# final_sch.net
KiCad netlist of a schematic drawn in Altium Designer
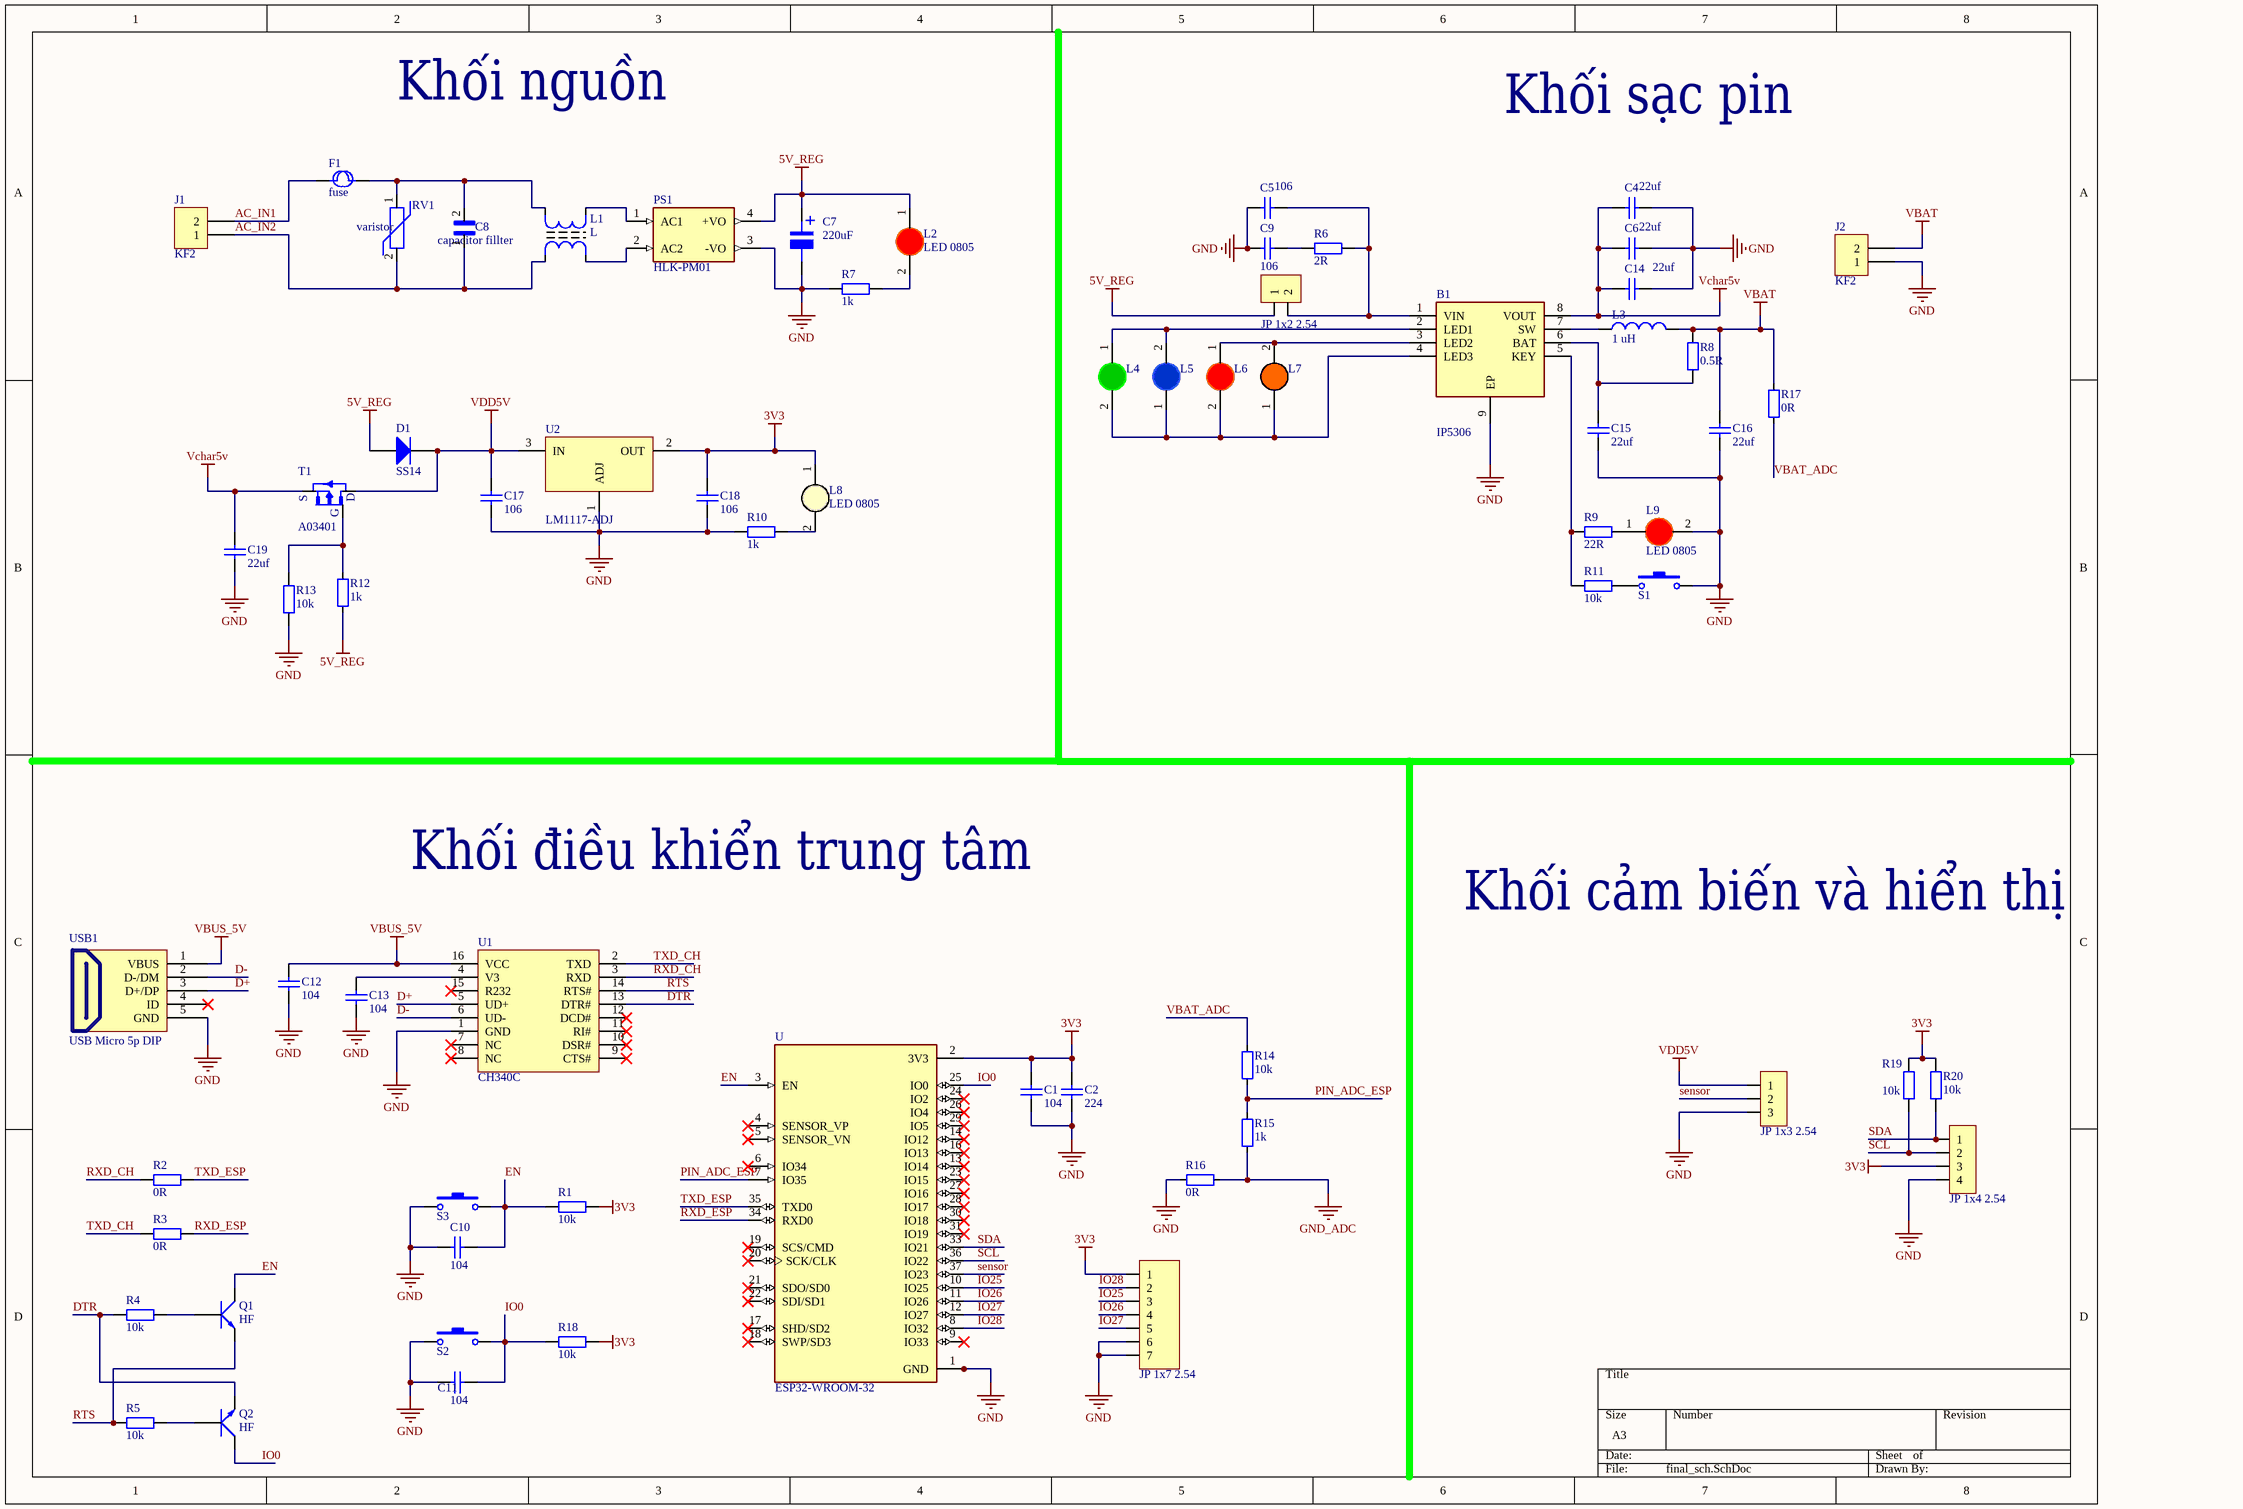
[diagram p0: final_sch.SchDoc]

(export (version "E")
  (design (tool "Eeschema 10.0.6"))
  (components
    (comp (ref "B1")
      (value "IP5306")
      (footprint "SOIC127P600X165-9N")
      (description "Fully-Integrated Power-Bank System-On-Chip")
      (libsource (lib "IP5306") (part "IP5306"))
    )
    (comp (ref "C1")
      (value "104")
      (footprint "tu 0805")
      (description "Dán")
      (libsource (lib "Altium_Lib_by_KhueNguyenCreator") (part "Tu 0805 104 50V 10%"))
    )
    (comp (ref "C2")
      (value "224")
      (footprint "tu 0805")
      (description "Dán")
      (libsource (lib "Altium_Lib_by_KhueNguyenCreator") (part "Tu 0805 224 50V 10%"))
    )
    (comp (ref "C4")
      (value "22uf")
      (footprint "tu 0805")
      (description "Dán")
      (libsource (lib "Altium_Lib_by_KhueNguyenCreator") (part "Tu 0805 225 25V 10%"))
    )
    (comp (ref "C5")
      (value "106")
      (footprint "tu 0805")
      (description "Dán")
      (libsource (lib "Altium_Lib_by_KhueNguyenCreator") (part "Tu 0805 106 16V 10%"))
    )
    (comp (ref "C6")
      (value "22uf")
      (footprint "tu 0805")
      (description "Dán")
      (libsource (lib "Altium_Lib_by_KhueNguyenCreator") (part "Tu 0805 225 25V 10%"))
    )
    (comp (ref "C7")
      (value "220uF")
      (footprint "tu nhom 10 (g)")
      (description "Dán")
      (libsource (lib "Altium_Lib_by_KhueNguyenCreator") (part "Tu Nhom 220uF 50V"))
    )
    (comp (ref "C8")
      (value "capacitor fillter")
      (footprint "CAPRR1000W60L1300T600H1200")
      (description "Safety Capacitors FILM CAP MKP X2 0.10uF 20% 305Vac LS 10mm - short leads")
      (fields (field (name "MP") "B32921C3104M003") (field (name "MF") "TDK"))
      (libsource (lib "B32921C3104M003") (part "B32921C3104M003"))
    )
    (comp (ref "C9")
      (value "106")
      (footprint "tu 0805")
      (description "Dán")
      (libsource (lib "Altium_Lib_by_KhueNguyenCreator") (part "Tu 0805 106 16V 10%"))
    )
    (comp (ref "C10")
      (value "104")
      (footprint "tu 0805")
      (description "Dán")
      (libsource (lib "Altium_Lib_by_KhueNguyenCreator") (part "Tu 0805 104 50V 10%"))
    )
    (comp (ref "C11")
      (value "104")
      (footprint "tu 0805")
      (description "Dán")
      (libsource (lib "Altium_Lib_by_KhueNguyenCreator") (part "Tu 0805 104 50V 10%"))
    )
    (comp (ref "C12")
      (value "104")
      (footprint "tu 0805")
      (description "Dán")
      (libsource (lib "Altium_Lib_by_KhueNguyenCreator") (part "Tu 0805 104 50V 10%"))
    )
    (comp (ref "C13")
      (value "104")
      (footprint "tu 0805")
      (description "Dán")
      (libsource (lib "Altium_Lib_by_KhueNguyenCreator") (part "Tu 0805 104 50V 10%"))
    )
    (comp (ref "C14")
      (value "22uf")
      (footprint "tu 0805")
      (description "Dán")
      (libsource (lib "Altium_Lib_by_KhueNguyenCreator") (part "Tu 0805 225 25V 10%"))
    )
    (comp (ref "C15")
      (value "22uf")
      (footprint "tu 0805")
      (description "Dán")
      (libsource (lib "Altium_Lib_by_KhueNguyenCreator") (part "Tu 0805 225 25V 10%"))
    )
    (comp (ref "C16")
      (value "22uf")
      (footprint "tu 0805")
      (description "Dán")
      (libsource (lib "Altium_Lib_by_KhueNguyenCreator") (part "Tu 0805 225 25V 10%"))
    )
    (comp (ref "C17")
      (value "106")
      (footprint "tu 0805")
      (description "Dán")
      (libsource (lib "Altium_Lib_by_KhueNguyenCreator") (part "Tu 0805 106 16V 10%"))
    )
    (comp (ref "C18")
      (value "106")
      (footprint "tu 0805")
      (description "Dán")
      (libsource (lib "Altium_Lib_by_KhueNguyenCreator") (part "Tu 0805 106 16V 10%"))
    )
    (comp (ref "C19")
      (value "22uf")
      (footprint "tu 0805")
      (description "Dán")
      (libsource (lib "Altium_Lib_by_KhueNguyenCreator") (part "Tu 0805 225 25V 10%"))
    )
    (comp (ref "D1")
      (value "SS14")
      (footprint "DIODE SMA")
      (description "Dán")
      (libsource (lib "Altium_Lib_by_KhueNguyenCreator") (part "Diode SS14 ( 1N5819)"))
    )
    (comp (ref "F1")
      (value "fuse")
      (footprint "F2-5.1-11.4X3.0X18.3MM")
      (description "Polymeric PTC Resettable Fuse 30V 2.5A Ih Through Hole Radial, Disc")
      (fields (field (name "MF") "Littelfuse") (field (name "MP") "30R250"))
      (libsource (lib "DIP-PPTC-2.5A-30V_D11.4MM_") (part "DIP-PPTC-2.5A-30V(D11.4MM)"))
    )
    (comp (ref "J1")
      (value "KF2")
      (footprint "KF2-3.5")
      (fields
        (field (name "MANUFACTURER") "Würth Elektronik eiSos GmbH")
        (field (name "PARTNO") "691103110002")
        (field (name "CREATED BY") "Karrer Zheng")
      )
      (libsource (lib "My Library") (part "KF2"))
    )
    (comp (ref "J2")
      (value "KF2")
      (footprint "KF2-3.5")
      (fields
        (field (name "MANUFACTURER") "Würth Elektronik eiSos GmbH")
        (field (name "PARTNO") "691103110002")
        (field (name "CREATED BY") "Karrer Zheng")
      )
      (libsource (lib "My Library") (part "KF2"))
    )
    (comp (ref "JP1")
      (value "JP 1x4 2.54")
      (footprint "JP 1x4 CT")
      (description "Cắm")
      (libsource (lib "Altium_Lib_by_KhueNguyenCreator") (part "JP 1x4 2.54 Cai Thang"))
    )
    (comp (ref "JP2")
      (value "JP 1x3 2.54")
      (footprint "JP 1x3 DT")
      (description "Cắm")
      (libsource (lib "Altium_Lib_by_KhueNguyenCreator") (part "JP 1x3 2.54 Duc Thang"))
    )
    (comp (ref "JP3")
      (value "JP 1x7 2.54")
      (footprint "JP 1x7 CT")
      (description "Cắm")
      (libsource (lib "Altium_Lib_by_KhueNguyenCreator") (part "JP 1x7 2.54 Cai Thang"))
    )
    (comp (ref "JP4")
      (value "JP 1x2 2.54")
      (footprint "JP 1x2 DT")
      (description "Cắm")
      (libsource (lib "Altium_Lib_by_KhueNguyenCreator") (part "JP 1x2 2.54 Duc Thang"))
    )
    (comp (ref "L1")
      (value "L")
      (footprint "L-DIP-220")
      (description "Inductor")
      (fields (field (name "DESIGNED BY") "VanDungEvn"))
      (libsource (lib "My Library") (part "L-DIP-220"))
    )
    (comp (ref "L2")
      (value "LED 0805")
      (footprint "LED-0805-Red")
      (description "Dán")
      (libsource (lib "Altium_Lib_by_KhueNguyenCreator") (part "LED 0805 Do"))
    )
    (comp (ref "L3")
      (value "1 uH")
      (footprint "IND_90.5_141.7_125X31_SMD")
      (description "Fixed Inductors WPN3012H1R0MT 100kHz")
      (fields
        (field (name "MANUFACTURER") "Sunlord")
        (field (name "MANUFACTURER PART NUMBER") "WPN3012H1R0MT")
      )
      (libsource (lib "Altium_Lib_by_KhueNguyenCreator") (part "IND_1uH-4.2A-20%-SMD"))
    )
    (comp (ref "L4")
      (value "~")
      (footprint "LED-0805-Green")
      (description "Dán")
      (libsource (lib "Altium_Lib_by_KhueNguyenCreator") (part "LED 0805 Xanh La"))
    )
    (comp (ref "L5")
      (value "~")
      (footprint "LED-0805-Blue")
      (description "Dán")
      (libsource (lib "Altium_Lib_by_KhueNguyenCreator") (part "LED 0805 Xanh Duong"))
    )
    (comp (ref "L6")
      (value "~")
      (footprint "LED-0805-Red")
      (description "Dán")
      (libsource (lib "Altium_Lib_by_KhueNguyenCreator") (part "LED 0805 Do"))
    )
    (comp (ref "L7")
      (value "~")
      (footprint "LED-0805-Orange")
      (description "Dán")
      (libsource (lib "Altium_Lib_by_KhueNguyenCreator") (part "LED 0805 Cam"))
    )
    (comp (ref "L8")
      (value "LED 0805")
      (footprint "LED-0805-Yellow")
      (description "Dán")
      (libsource (lib "Altium_Lib_by_KhueNguyenCreator") (part "LED 0805 Trang"))
    )
    (comp (ref "L9")
      (value "LED 0805")
      (footprint "LED-0805-Red")
      (description "Dán")
      (libsource (lib "Altium_Lib_by_KhueNguyenCreator") (part "LED 0805 Do"))
    )
    (comp (ref "PS1")
      (value "HLK-PM01")
      (footprint "CONV_HLK-PM01")
      (fields (field (name "MF") "Hi-link") (field (name "MP") "hlk-pm01"))
      (libsource (lib "HLK-PM01") (part "HLK-PM01"))
    )
    (comp (ref "Q1")
      (value "HF")
      (footprint "SOT23")
      (description "NPN transistor")
      (libsource (lib "Altium_Lib_by_KhueNguyenCreator") (part "C1815 HF SMD"))
    )
    (comp (ref "Q2")
      (value "HF")
      (footprint "SOT23")
      (description "NPN transistor")
      (libsource (lib "Altium_Lib_by_KhueNguyenCreator") (part "C1815 HF SMD"))
    )
    (comp (ref "R1")
      (value "10k")
      (footprint "tro smd 0805")
      (description "Dán")
      (libsource (lib "Altium_Lib_by_KhueNguyenCreator") (part "Tro 0805 5% 10k"))
    )
    (comp (ref "R2")
      (value "0R")
      (footprint "tro smd 0805")
      (description "Dán")
      (libsource (lib "Altium_Lib_by_KhueNguyenCreator") (part "Tro 0805 5% 0R"))
    )
    (comp (ref "R3")
      (value "0R")
      (footprint "tro smd 0805")
      (description "Dán")
      (libsource (lib "Altium_Lib_by_KhueNguyenCreator") (part "Tro 0805 5% 0R"))
    )
    (comp (ref "R4")
      (value "10k")
      (footprint "tro smd 0805")
      (description "Dán")
      (libsource (lib "Altium_Lib_by_KhueNguyenCreator") (part "Tro 0805 5% 10k"))
    )
    (comp (ref "R5")
      (value "10k")
      (footprint "tro smd 0805")
      (description "Dán")
      (libsource (lib "Altium_Lib_by_KhueNguyenCreator") (part "Tro 0805 5% 10k"))
    )
    (comp (ref "R6")
      (value "2R")
      (footprint "tro smd 0805")
      (description "Dán")
      (libsource (lib "Altium_Lib_by_KhueNguyenCreator") (part "Tro 0805 5% 1R"))
    )
    (comp (ref "R7")
      (value "1k")
      (footprint "tro smd 0805")
      (description "Dán")
      (libsource (lib "Altium_Lib_by_KhueNguyenCreator") (part "Tro 0805 1% 1k"))
    )
    (comp (ref "R8")
      (value "0.5R")
      (footprint "tro smd 0805")
      (description "Dán")
      (libsource (lib "Altium_Lib_by_KhueNguyenCreator") (part "Tro 0805 1% 0.5R"))
    )
    (comp (ref "R9")
      (value "22R")
      (footprint "tro smd 0805")
      (description "Dán")
      (libsource (lib "Altium_Lib_by_KhueNguyenCreator") (part "Tro 0805 5% 22R"))
    )
    (comp (ref "R10")
      (value "1k")
      (footprint "tro smd 0805")
      (description "Dán")
      (libsource (lib "Altium_Lib_by_KhueNguyenCreator") (part "Tro 0805 1% 1k"))
    )
    (comp (ref "R11")
      (value "10k")
      (footprint "tro smd 0805")
      (description "Dán")
      (libsource (lib "Altium_Lib_by_KhueNguyenCreator") (part "Tro 0805 1% 10k"))
    )
    (comp (ref "R12")
      (value "1k")
      (footprint "RES-SMD-0805")
      (description "Resistor")
      (fields
        (field (name "MANUFACTURER") "Generic Components")
        (field (name "PUBLISHER") "Altium Hobart Technology Centre")
      )
      (libsource (lib "My Library") (part "Resistor - SMD"))
    )
    (comp (ref "R13")
      (value "10k")
      (footprint "tro smd 0805")
      (description "Dán")
      (libsource (lib "Altium_Lib_by_KhueNguyenCreator") (part "Tro 0805 1% 10k"))
    )
    (comp (ref "R14")
      (value "10k")
      (footprint "RES-SMD-0805")
      (description "Resistor")
      (fields
        (field (name "MANUFACTURER") "Generic Components")
        (field (name "PUBLISHER") "Altium Hobart Technology Centre")
      )
      (libsource (lib "My Library") (part "Resistor - SMD"))
    )
    (comp (ref "R15")
      (value "1k")
      (footprint "RES-SMD-0805")
      (description "Resistor")
      (fields
        (field (name "MANUFACTURER") "Generic Components")
        (field (name "PUBLISHER") "Altium Hobart Technology Centre")
      )
      (libsource (lib "My Library") (part "Resistor - SMD"))
    )
    (comp (ref "R16")
      (value "0R")
      (footprint "RES-SMD-0805")
      (description "Resistor")
      (fields
        (field (name "MANUFACTURER") "Generic Components")
        (field (name "PUBLISHER") "Altium Hobart Technology Centre")
      )
      (libsource (lib "My Library") (part "Resistor - SMD"))
    )
    (comp (ref "R17")
      (value "0R")
      (footprint "RES-SMD-0805")
      (description "Resistor")
      (fields
        (field (name "MANUFACTURER") "Generic Components")
        (field (name "PUBLISHER") "Altium Hobart Technology Centre")
      )
      (libsource (lib "My Library") (part "Resistor - SMD"))
    )
    (comp (ref "R18")
      (value "10k")
      (footprint "tro smd 0805")
      (description "Dán")
      (libsource (lib "Altium_Lib_by_KhueNguyenCreator") (part "Tro 0805 5% 10k"))
    )
    (comp (ref "R19")
      (value "10k")
      (footprint "tro smd 0805")
      (description "Dán")
      (libsource (lib "Altium_Lib_by_KhueNguyenCreator") (part "Tro 0805 1% 10k"))
    )
    (comp (ref "R20")
      (value "10k")
      (footprint "tro smd 0805")
      (description "Dán")
      (libsource (lib "Altium_Lib_by_KhueNguyenCreator") (part "Tro 0805 1% 10k"))
    )
    (comp (ref "RV1")
      (value "varistor")
      (footprint "MOV14D471K")
      (description "470 V 4.5 kA Varistor 1 Circuit Through Hole Disc 14mm")
      (fields (field (name "MP") "MOV-14D471K") (field (name "MF") "Bourns"))
      (libsource (lib "varistor") (part "MOV-14D471K"))
    )
    (comp (ref "S1")
      (value "SW-SMD")
      (footprint "SW-SMD")
      (description "Switch")
      (fields (field (name "PUBLISHER") "Altium Limited"))
      (libsource (lib "My Library") (part "SW-SMD"))
    )
    (comp (ref "S2")
      (value "SW-SMD")
      (footprint "SW-SMD")
      (description "Switch")
      (fields (field (name "PUBLISHER") "Altium Limited"))
      (libsource (lib "My Library") (part "SW-SMD"))
    )
    (comp (ref "S3")
      (value "SW-SMD")
      (footprint "SW-SMD")
      (description "Switch")
      (fields (field (name "PUBLISHER") "Altium Limited"))
      (libsource (lib "My Library") (part "SW-SMD"))
    )
    (comp (ref "T1")
      (value "A03401")
      (footprint "My Library:A3401")
      (description "P-Channel 30V 4A _Ta_ 1.4W _Ta_ Surface Mount SOT-23-3")
      (libsource (lib "My Library") (part "A03401"))
    )
    (comp (ref "U")
      (value "ESP32-WROOM-32")
      (footprint "MODULE_ESP32-WROOM-32")
      (description "Bluetooth, WiFi Transceiver Module 2.4GHz ~ 2.5GHz Surface Mount")
      (fields (field (name "MF") "Espressif Systems") (field (name "DIGI-KEY_PART_NUMBER") "1904-1010-1-ND"))
      (libsource (lib "My Library") (part "ESP32-WROOM-32"))
    )
    (comp (ref "U1")
      (value "CH340C")
      (footprint "SOIC16_50_284_25X90_SMT")
      (description "USB Bridge, USB to UART USB 2.0 UART Interface")
      (fields (field (name "MANUFACTURER") "Olimex"))
      (libsource (lib "Altium_Lib_by_KhueNguyenCreator") (part "CH340C"))
    )
    (comp (ref "U2")
      (value "LM1117-ADJ")
      (footprint "LM1117-SOP")
      (description "800mA Low-Dropout Linear Regulator")
      (fields (field (name "CREATOR") "Nguyen Ba Bien"))
      (libsource (lib "My Library") (part "LM1117-ADJ"))
    )
    (comp (ref "USB1")
      (value "USB Micro 5p DIP")
      (footprint "USB Micro 5p DIP")
      (description "USB Type B")
      (libsource (lib "Altium_Lib_by_KhueNguyenCreator") (part "USB Micro 5p DIP"))
    )
  )
  (nets
    (net (code "1") (name "/AC_IN1") (class "Default")
      (node (ref "F1") (pin "1") (pinfunction "1_1") (pintype "bidirectional"))
      (node (ref "J1") (pin "2") (pinfunction "2_2") (pintype "passive"))
    )
    (net (code "2") (name "/AC_IN2") (class "Default")
      (node (ref "C8") (pin "1") (pinfunction "1_1") (pintype "passive"))
      (node (ref "J1") (pin "1") (pinfunction "1_1") (pintype "passive"))
      (node (ref "L1") (pin "1") (pinfunction "1_1") (pintype "passive"))
      (node (ref "RV1") (pin "2") (pinfunction "2_2") (pintype "bidirectional"))
    )
    (net (code "3") (name "/D+") (class "Default")
      (node (ref "U1") (pin "5") (pinfunction "UD+_5") (pintype "passive"))
      (node (ref "USB1") (pin "3") (pinfunction "D+/DP_3") (pintype "passive"))
    )
    (net (code "4") (name "/D-") (class "Default")
      (node (ref "U1") (pin "6") (pinfunction "UD-_6") (pintype "passive"))
      (node (ref "USB1") (pin "2") (pinfunction "D-/DM_2") (pintype "passive"))
    )
    (net (code "5") (name "/DTR") (class "Default")
      (node (ref "Q2") (pin "2") (pinfunction "E_2") (pintype "passive"))
      (node (ref "R4") (pin "2") (pinfunction "2_2") (pintype "passive"))
      (node (ref "U1") (pin "13") (pinfunction "DTR#_13") (pintype "passive"))
    )
    (net (code "6") (name "/EN") (class "Default")
      (node (ref "C10") (pin "1") (pinfunction "1_1") (pintype "passive"))
      (node (ref "Q1") (pin "3") (pinfunction "C_3") (pintype "passive"))
      (node (ref "R1") (pin "1") (pinfunction "1_1") (pintype "passive"))
      (node (ref "S3") (pin "2") (pinfunction "2_2") (pintype "passive"))
      (node (ref "U") (pin "3") (pinfunction "EN_3") (pintype "input"))
    )
    (net (code "7") (name "/IO0") (class "Default")
      (node (ref "C11") (pin "1") (pinfunction "1_1") (pintype "passive"))
      (node (ref "Q2") (pin "3") (pinfunction "C_3") (pintype "passive"))
      (node (ref "R18") (pin "2") (pinfunction "2_2") (pintype "passive"))
      (node (ref "S2") (pin "2") (pinfunction "2_2") (pintype "passive"))
      (node (ref "U") (pin "25") (pinfunction "IO0_25") (pintype "bidirectional"))
    )
    (net (code "8") (name "/IO25") (class "Default")
      (node (ref "JP3") (pin "3") (pinfunction "3_3") (pintype "passive"))
      (node (ref "U") (pin "10") (pinfunction "IO25_10") (pintype "bidirectional"))
    )
    (net (code "9") (name "/IO26") (class "Default")
      (node (ref "JP3") (pin "4") (pinfunction "4_4") (pintype "passive"))
      (node (ref "U") (pin "11") (pinfunction "IO26_11") (pintype "bidirectional"))
    )
    (net (code "10") (name "/IO27") (class "Default")
      (node (ref "JP3") (pin "5") (pinfunction "5_5") (pintype "passive"))
      (node (ref "U") (pin "12") (pinfunction "IO27_12") (pintype "bidirectional"))
    )
    (net (code "11") (name "/IO28") (class "Default")
      (node (ref "JP3") (pin "2") (pinfunction "2_2") (pintype "passive"))
      (node (ref "U") (pin "8") (pinfunction "IO32_8") (pintype "bidirectional"))
    )
    (net (code "12") (name "/PIN_ADC_ESP") (class "Default")
      (node (ref "R14") (pin "1") (pinfunction "1_1") (pintype "passive"))
      (node (ref "R15") (pin "2") (pinfunction "2_2") (pintype "passive"))
      (node (ref "U") (pin "7") (pinfunction "IO35_7") (pintype "input"))
    )
    (net (code "13") (name "/RTS") (class "Default")
      (node (ref "Q1") (pin "2") (pinfunction "E_2") (pintype "passive"))
      (node (ref "R5") (pin "2") (pinfunction "2_2") (pintype "passive"))
      (node (ref "U1") (pin "14") (pinfunction "RTS#_14") (pintype "passive"))
    )
    (net (code "14") (name "/RXD_CH") (class "Default")
      (node (ref "R2") (pin "1") (pinfunction "1_1") (pintype "passive"))
      (node (ref "U1") (pin "3") (pinfunction "RXD_3") (pintype "passive"))
    )
    (net (code "15") (name "/RXD_ESP") (class "Default")
      (node (ref "R3") (pin "2") (pinfunction "2_2") (pintype "passive"))
      (node (ref "U") (pin "34") (pinfunction "RXD0_34") (pintype "bidirectional"))
    )
    (net (code "16") (name "/SCL") (class "Default")
      (node (ref "JP1") (pin "2") (pinfunction "2_2") (pintype "passive"))
      (node (ref "R19") (pin "2") (pinfunction "2_2") (pintype "passive"))
      (node (ref "U") (pin "36") (pinfunction "IO22_36") (pintype "bidirectional"))
    )
    (net (code "17") (name "/SDA") (class "Default")
      (node (ref "JP1") (pin "1") (pinfunction "1_1") (pintype "passive"))
      (node (ref "R20") (pin "2") (pinfunction "2_2") (pintype "passive"))
      (node (ref "U") (pin "33") (pinfunction "IO21_33") (pintype "bidirectional"))
    )
    (net (code "18") (name "/TXD_CH") (class "Default")
      (node (ref "R3") (pin "1") (pinfunction "1_1") (pintype "passive"))
      (node (ref "U1") (pin "2") (pinfunction "TXD_2") (pintype "passive"))
    )
    (net (code "19") (name "/TXD_ESP") (class "Default")
      (node (ref "R2") (pin "2") (pinfunction "2_2") (pintype "passive"))
      (node (ref "U") (pin "35") (pinfunction "TXD0_35") (pintype "bidirectional"))
    )
    (net (code "20") (name "/VBAT_ADC") (class "Default")
      (node (ref "R14") (pin "2") (pinfunction "2_2") (pintype "passive"))
      (node (ref "R17") (pin "2") (pinfunction "2_2") (pintype "passive"))
    )
    (net (code "21") (name "/sensor") (class "Default")
      (node (ref "JP2") (pin "2") (pinfunction "2_2") (pintype "passive"))
      (node (ref "U") (pin "37") (pinfunction "IO23_37") (pintype "bidirectional"))
    )
    (net (code "22") (name "3V3") (class "Default")
      (node (ref "C1") (pin "2") (pinfunction "2_2") (pintype "passive"))
      (node (ref "C18") (pin "1") (pinfunction "1_1") (pintype "passive"))
      (node (ref "C2") (pin "1") (pinfunction "1_1") (pintype "passive"))
      (node (ref "JP1") (pin "3") (pinfunction "3_3") (pintype "passive"))
      (node (ref "JP3") (pin "1") (pinfunction "1_1") (pintype "passive"))
      (node (ref "L8") (pin "1") (pinfunction "A_1") (pintype "passive"))
      (node (ref "R1") (pin "2") (pinfunction "2_2") (pintype "passive"))
      (node (ref "R18") (pin "1") (pinfunction "1_1") (pintype "passive"))
      (node (ref "R19") (pin "1") (pinfunction "1_1") (pintype "passive"))
      (node (ref "R20") (pin "1") (pinfunction "1_1") (pintype "passive"))
      (node (ref "U") (pin "2") (pinfunction "3V3_2") (pintype "power_in"))
      (node (ref "U2") (pin "2") (pinfunction "OUT_2") (pintype "passive"))
    )
    (net (code "23") (name "5V_REG") (class "Default")
      (node (ref "C7") (pin "1") (pinfunction "1_1") (pintype "passive"))
      (node (ref "D1") (pin "1") (pinfunction "A_1") (pintype "passive"))
      (node (ref "JP4") (pin "1") (pinfunction "1_1") (pintype "passive"))
      (node (ref "L2") (pin "1") (pinfunction "A_1") (pintype "passive"))
      (node (ref "PS1") (pin "4") (pinfunction "+VO_4") (pintype "output"))
      (node (ref "R12") (pin "1") (pinfunction "1_1") (pintype "passive"))
    )
    (net (code "24") (name "GND") (class "Default")
      (node (ref "B1") (pin "9") (pinfunction "EP_9") (pintype "passive"))
      (node (ref "C1") (pin "1") (pinfunction "1_1") (pintype "passive"))
      (node (ref "C10") (pin "2") (pinfunction "2_2") (pintype "passive"))
      (node (ref "C11") (pin "2") (pinfunction "2_2") (pintype "passive"))
      (node (ref "C12") (pin "2") (pinfunction "2_2") (pintype "passive"))
      (node (ref "C13") (pin "2") (pinfunction "2_2") (pintype "passive"))
      (node (ref "C14") (pin "2") (pinfunction "2_2") (pintype "passive"))
      (node (ref "C15") (pin "1") (pinfunction "1_1") (pintype "passive"))
      (node (ref "C16") (pin "2") (pinfunction "2_2") (pintype "passive"))
      (node (ref "C17") (pin "2") (pinfunction "2_2") (pintype "passive"))
      (node (ref "C18") (pin "2") (pinfunction "2_2") (pintype "passive"))
      (node (ref "C19") (pin "2") (pinfunction "2_2") (pintype "passive"))
      (node (ref "C2") (pin "2") (pinfunction "2_2") (pintype "passive"))
      (node (ref "C4") (pin "1") (pinfunction "1_1") (pintype "passive"))
      (node (ref "C5") (pin "2") (pinfunction "2_2") (pintype "passive"))
      (node (ref "C6") (pin "1") (pinfunction "1_1") (pintype "passive"))
      (node (ref "C7") (pin "2") (pinfunction "2_2") (pintype "passive"))
      (node (ref "C9") (pin "2") (pinfunction "2_2") (pintype "passive"))
      (node (ref "J2") (pin "1") (pinfunction "1_1") (pintype "passive"))
      (node (ref "JP1") (pin "4") (pinfunction "4_4") (pintype "passive"))
      (node (ref "JP2") (pin "3") (pinfunction "3_3") (pintype "passive"))
      (node (ref "JP3") (pin "6") (pinfunction "6_6") (pintype "passive"))
      (node (ref "JP3") (pin "7") (pinfunction "7_7") (pintype "passive"))
      (node (ref "L9") (pin "2") (pinfunction "K_2") (pintype "passive"))
      (node (ref "PS1") (pin "3") (pinfunction "-VO_3") (pintype "output"))
      (node (ref "R10") (pin "2") (pinfunction "2_2") (pintype "passive"))
      (node (ref "R13") (pin "1") (pinfunction "1_1") (pintype "passive"))
      (node (ref "R16") (pin "2") (pinfunction "2_2") (pintype "passive"))
      (node (ref "R7") (pin "2") (pinfunction "2_2") (pintype "passive"))
      (node (ref "S1") (pin "2") (pinfunction "2_2") (pintype "passive"))
      (node (ref "S2") (pin "1") (pinfunction "1_1") (pintype "passive"))
      (node (ref "S3") (pin "1") (pinfunction "1_1") (pintype "passive"))
      (node (ref "U") (pin "1") (pinfunction "GND_1") (pintype "power_in"))
      (node (ref "U") (pin "15") (pinfunction "GND_15") (pintype "power_in"))
      (node (ref "U") (pin "38") (pinfunction "GND_38") (pintype "power_in"))
      (node (ref "U") (pin "39_1") (pinfunction "GND_39_1") (pintype "power_in"))
      (node (ref "U") (pin "39_10") (pinfunction "GND_39_10") (pintype "power_in"))
      (node (ref "U") (pin "39_11") (pinfunction "GND_39_11") (pintype "power_in"))
      (node (ref "U") (pin "39_12") (pinfunction "GND_39_12") (pintype "power_in"))
      (node (ref "U") (pin "39_13") (pinfunction "GND_39_13") (pintype "power_in"))
      (node (ref "U") (pin "39_14") (pinfunction "GND_39_14") (pintype "power_in"))
      (node (ref "U") (pin "39_15") (pinfunction "GND_39_15") (pintype "power_in"))
      (node (ref "U") (pin "39_16") (pinfunction "GND_39_16") (pintype "power_in"))
      (node (ref "U") (pin "39_17") (pinfunction "GND_39_17") (pintype "power_in"))
      (node (ref "U") (pin "39_18") (pinfunction "GND_39_18") (pintype "power_in"))
      (node (ref "U") (pin "39_19") (pinfunction "GND_39_19") (pintype "power_in"))
      (node (ref "U") (pin "39_2") (pinfunction "GND_39_2") (pintype "power_in"))
      (node (ref "U") (pin "39_20") (pinfunction "GND_39_20") (pintype "power_in"))
      (node (ref "U") (pin "39_21") (pinfunction "GND_39_21") (pintype "power_in"))
      (node (ref "U") (pin "39_3") (pinfunction "GND_39_3") (pintype "power_in"))
      (node (ref "U") (pin "39_4") (pinfunction "GND_39_4") (pintype "power_in"))
      (node (ref "U") (pin "39_5") (pinfunction "GND_39_5") (pintype "power_in"))
      (node (ref "U") (pin "39_6") (pinfunction "GND_39_6") (pintype "power_in"))
      (node (ref "U") (pin "39_7") (pinfunction "GND_39_7") (pintype "power_in"))
      (node (ref "U") (pin "39_8") (pinfunction "GND_39_8") (pintype "power_in"))
      (node (ref "U") (pin "39_9") (pinfunction "GND_39_9") (pintype "power_in"))
      (node (ref "U1") (pin "1") (pinfunction "GND_1") (pintype "passive"))
      (node (ref "U2") (pin "1") (pinfunction "ADJ_1") (pintype "passive"))
      (node (ref "USB1") (pin "5") (pinfunction "GND_5") (pintype "passive"))
    )
    (net (code "25") (name "GND_ADC") (class "Default")
      (node (ref "R15") (pin "1") (pinfunction "1_1") (pintype "passive"))
      (node (ref "R16") (pin "1") (pinfunction "1_1") (pintype "passive"))
    )
    (net (code "26") (name "Net-(B1-BAT)") (class "Default")
      (node (ref "B1") (pin "6") (pinfunction "BAT_6") (pintype "passive"))
      (node (ref "C15") (pin "2") (pinfunction "2_2") (pintype "passive"))
      (node (ref "R8") (pin "1") (pinfunction "1_1") (pintype "passive"))
    )
    (net (code "27") (name "Net-(B1-KEY)") (class "Default")
      (node (ref "B1") (pin "5") (pinfunction "KEY_5") (pintype "passive"))
      (node (ref "R11") (pin "1") (pinfunction "1_1") (pintype "passive"))
      (node (ref "R9") (pin "1") (pinfunction "1_1") (pintype "passive"))
    )
    (net (code "28") (name "Net-(B1-LED1)") (class "Default")
      (node (ref "B1") (pin "2") (pinfunction "LED1_2") (pintype "passive"))
      (node (ref "L4") (pin "1") (pinfunction "A_1") (pintype "passive"))
      (node (ref "L5") (pin "2") (pinfunction "K_2") (pintype "passive"))
    )
    (net (code "29") (name "Net-(B1-LED2)") (class "Default")
      (node (ref "B1") (pin "3") (pinfunction "LED2_3") (pintype "passive"))
      (node (ref "L6") (pin "1") (pinfunction "A_1") (pintype "passive"))
      (node (ref "L7") (pin "2") (pinfunction "K_2") (pintype "passive"))
    )
    (net (code "30") (name "Net-(B1-LED3)") (class "Default")
      (node (ref "B1") (pin "4") (pinfunction "LED3_4") (pintype "passive"))
      (node (ref "L4") (pin "2") (pinfunction "K_2") (pintype "passive"))
      (node (ref "L5") (pin "1") (pinfunction "A_1") (pintype "passive"))
      (node (ref "L6") (pin "2") (pinfunction "K_2") (pintype "passive"))
      (node (ref "L7") (pin "1") (pinfunction "A_1") (pintype "passive"))
    )
    (net (code "31") (name "Net-(B1-SW)") (class "Default")
      (node (ref "B1") (pin "7") (pinfunction "SW_7") (pintype "passive"))
      (node (ref "L3") (pin "1") (pinfunction "1_1") (pintype "passive"))
    )
    (net (code "32") (name "Net-(B1-VIN)") (class "Default")
      (node (ref "B1") (pin "1") (pinfunction "VIN_1") (pintype "passive"))
      (node (ref "C5") (pin "1") (pinfunction "1_1") (pintype "passive"))
      (node (ref "JP4") (pin "2") (pinfunction "2_2") (pintype "passive"))
      (node (ref "R6") (pin "2") (pinfunction "2_2") (pintype "passive"))
    )
    (net (code "33") (name "Net-(C8-Pad2)") (class "Default")
      (node (ref "C8") (pin "2") (pinfunction "2_2") (pintype "passive"))
      (node (ref "F1") (pin "2") (pinfunction "2_2") (pintype "bidirectional"))
      (node (ref "L1") (pin "4") (pinfunction "4_4") (pintype "passive"))
      (node (ref "RV1") (pin "1") (pinfunction "1_1") (pintype "bidirectional"))
    )
    (net (code "34") (name "Net-(C9-Pad1)") (class "Default")
      (node (ref "C9") (pin "1") (pinfunction "1_1") (pintype "passive"))
      (node (ref "R6") (pin "1") (pinfunction "1_1") (pintype "passive"))
    )
    (net (code "35") (name "Net-(L2-K)") (class "Default")
      (node (ref "L2") (pin "2") (pinfunction "K_2") (pintype "passive"))
      (node (ref "R7") (pin "1") (pinfunction "1_1") (pintype "passive"))
    )
    (net (code "36") (name "Net-(L8-K)") (class "Default")
      (node (ref "L8") (pin "2") (pinfunction "K_2") (pintype "passive"))
      (node (ref "R10") (pin "1") (pinfunction "1_1") (pintype "passive"))
    )
    (net (code "37") (name "Net-(L9-A)") (class "Default")
      (node (ref "L9") (pin "1") (pinfunction "A_1") (pintype "passive"))
      (node (ref "R9") (pin "2") (pinfunction "2_2") (pintype "passive"))
    )
    (net (code "38") (name "Net-(PS1-AC1)") (class "Default")
      (node (ref "L1") (pin "3") (pinfunction "3_3") (pintype "passive"))
      (node (ref "PS1") (pin "1") (pinfunction "AC1_1") (pintype "input"))
    )
    (net (code "39") (name "Net-(PS1-AC2)") (class "Default")
      (node (ref "L1") (pin "2") (pinfunction "2_2") (pintype "passive"))
      (node (ref "PS1") (pin "2") (pinfunction "AC2_2") (pintype "input"))
    )
    (net (code "40") (name "Net-(Q1-B)") (class "Default")
      (node (ref "Q1") (pin "1") (pinfunction "B_1") (pintype "passive"))
      (node (ref "R4") (pin "1") (pinfunction "1_1") (pintype "passive"))
    )
    (net (code "41") (name "Net-(Q2-B)") (class "Default")
      (node (ref "Q2") (pin "1") (pinfunction "B_1") (pintype "passive"))
      (node (ref "R5") (pin "1") (pinfunction "1_1") (pintype "passive"))
    )
    (net (code "42") (name "Net-(R11-Pad2)") (class "Default")
      (node (ref "R11") (pin "2") (pinfunction "2_2") (pintype "passive"))
      (node (ref "S1") (pin "1") (pinfunction "1_1") (pintype "passive"))
    )
    (net (code "43") (name "Net-(T1-G)") (class "Default")
      (node (ref "R12") (pin "2") (pinfunction "2_2") (pintype "passive"))
      (node (ref "R13") (pin "2") (pinfunction "2_2") (pintype "passive"))
      (node (ref "T1") (pin "1") (pinfunction "G_1") (pintype "passive"))
    )
    (net (code "44") (name "Net-(U1-V3)") (class "Default")
      (node (ref "C13") (pin "1") (pinfunction "1_1") (pintype "passive"))
      (node (ref "U1") (pin "4") (pinfunction "V3_4") (pintype "passive"))
    )
    (net (code "45") (name "VBAT") (class "Default")
      (node (ref "C16") (pin "1") (pinfunction "1_1") (pintype "passive"))
      (node (ref "J2") (pin "2") (pinfunction "2_2") (pintype "passive"))
      (node (ref "L3") (pin "2") (pinfunction "2_2") (pintype "passive"))
      (node (ref "R17") (pin "1") (pinfunction "1_1") (pintype "passive"))
      (node (ref "R8") (pin "2") (pinfunction "2_2") (pintype "passive"))
    )
    (net (code "46") (name "VBUS_5V") (class "Default")
      (node (ref "C12") (pin "1") (pinfunction "1_1") (pintype "passive"))
      (node (ref "U1") (pin "16") (pinfunction "VCC_16") (pintype "passive"))
      (node (ref "USB1") (pin "1") (pinfunction "VBUS_1") (pintype "passive"))
    )
    (net (code "47") (name "VDD5V") (class "Default")
      (node (ref "C17") (pin "1") (pinfunction "1_1") (pintype "passive"))
      (node (ref "D1") (pin "2") (pinfunction "K_2") (pintype "passive"))
      (node (ref "JP2") (pin "1") (pinfunction "1_1") (pintype "passive"))
      (node (ref "T1") (pin "3") (pinfunction "D_3") (pintype "passive"))
      (node (ref "U2") (pin "3") (pinfunction "IN_3") (pintype "passive"))
    )
    (net (code "48") (name "Vchar5v") (class "Default")
      (node (ref "B1") (pin "8") (pinfunction "VOUT_8") (pintype "passive"))
      (node (ref "C14") (pin "1") (pinfunction "1_1") (pintype "passive"))
      (node (ref "C19") (pin "1") (pinfunction "1_1") (pintype "passive"))
      (node (ref "C4") (pin "2") (pinfunction "2_2") (pintype "passive"))
      (node (ref "C6") (pin "2") (pinfunction "2_2") (pintype "passive"))
      (node (ref "T1") (pin "2") (pinfunction "S_2") (pintype "passive"))
    )
    (net (code "49") (name "unconnected-(U-IO2-Pad24)") (class "Default")
      (node (ref "U") (pin "24") (pinfunction "IO2_24") (pintype "bidirectional+no_connect"))
    )
    (net (code "50") (name "unconnected-(U-IO4-Pad26)") (class "Default")
      (node (ref "U") (pin "26") (pinfunction "IO4_26") (pintype "bidirectional+no_connect"))
    )
    (net (code "51") (name "unconnected-(U-IO5-Pad29)") (class "Default")
      (node (ref "U") (pin "29") (pinfunction "IO5_29") (pintype "bidirectional+no_connect"))
    )
    (net (code "52") (name "unconnected-(U-IO12-Pad14)") (class "Default")
      (node (ref "U") (pin "14") (pinfunction "IO12_14") (pintype "bidirectional+no_connect"))
    )
    (net (code "53") (name "unconnected-(U-IO13-Pad16)") (class "Default")
      (node (ref "U") (pin "16") (pinfunction "IO13_16") (pintype "bidirectional+no_connect"))
    )
    (net (code "54") (name "unconnected-(U-IO14-Pad13)") (class "Default")
      (node (ref "U") (pin "13") (pinfunction "IO14_13") (pintype "bidirectional+no_connect"))
    )
    (net (code "55") (name "unconnected-(U-IO15-Pad23)") (class "Default")
      (node (ref "U") (pin "23") (pinfunction "IO15_23") (pintype "bidirectional+no_connect"))
    )
    (net (code "56") (name "unconnected-(U-IO16-Pad27)") (class "Default")
      (node (ref "U") (pin "27") (pinfunction "IO16_27") (pintype "bidirectional+no_connect"))
    )
    (net (code "57") (name "unconnected-(U-IO17-Pad28)") (class "Default")
      (node (ref "U") (pin "28") (pinfunction "IO17_28") (pintype "bidirectional+no_connect"))
    )
    (net (code "58") (name "unconnected-(U-IO18-Pad30)") (class "Default")
      (node (ref "U") (pin "30") (pinfunction "IO18_30") (pintype "bidirectional+no_connect"))
    )
    (net (code "59") (name "unconnected-(U-IO19-Pad31)") (class "Default")
      (node (ref "U") (pin "31") (pinfunction "IO19_31") (pintype "bidirectional+no_connect"))
    )
    (net (code "60") (name "unconnected-(U-IO33-Pad9)") (class "Default")
      (node (ref "U") (pin "9") (pinfunction "IO33_9") (pintype "bidirectional+no_connect"))
    )
    (net (code "61") (name "unconnected-(U-IO34-Pad6)") (class "Default")
      (node (ref "U") (pin "6") (pinfunction "IO34_6") (pintype "input+no_connect"))
    )
    (net (code "62") (name "unconnected-(U-SCK{slash}CLK-Pad20)") (class "Default")
      (node (ref "U") (pin "20") (pinfunction "SCK/CLK_20") (pintype "bidirectional+no_connect"))
    )
    (net (code "63") (name "unconnected-(U-SCS{slash}CMD-Pad19)") (class "Default")
      (node (ref "U") (pin "19") (pinfunction "SCS/CMD_19") (pintype "bidirectional+no_connect"))
    )
    (net (code "64") (name "unconnected-(U-SDI{slash}SD1-Pad22)") (class "Default")
      (node (ref "U") (pin "22") (pinfunction "SDI/SD1_22") (pintype "bidirectional+no_connect"))
    )
    (net (code "65") (name "unconnected-(U-SDO{slash}SD0-Pad21)") (class "Default")
      (node (ref "U") (pin "21") (pinfunction "SDO/SD0_21") (pintype "bidirectional+no_connect"))
    )
    (net (code "66") (name "unconnected-(U-SENSOR_VN-Pad5)") (class "Default")
      (node (ref "U") (pin "5") (pinfunction "SENSOR_VN_5") (pintype "input+no_connect"))
    )
    (net (code "67") (name "unconnected-(U-SENSOR_VP-Pad4)") (class "Default")
      (node (ref "U") (pin "4") (pinfunction "SENSOR_VP_4") (pintype "input+no_connect"))
    )
    (net (code "68") (name "unconnected-(U-SHD{slash}SD2-Pad17)") (class "Default")
      (node (ref "U") (pin "17") (pinfunction "SHD/SD2_17") (pintype "bidirectional+no_connect"))
    )
    (net (code "69") (name "unconnected-(U-SWP{slash}SD3-Pad18)") (class "Default")
      (node (ref "U") (pin "18") (pinfunction "SWP/SD3_18") (pintype "bidirectional+no_connect"))
    )
    (net (code "70") (name "unconnected-(U1-CTS#-Pad9)") (class "Default")
      (node (ref "U1") (pin "9") (pinfunction "CTS#_9") (pintype "passive+no_connect"))
    )
    (net (code "71") (name "unconnected-(U1-DCD#-Pad12)") (class "Default")
      (node (ref "U1") (pin "12") (pinfunction "DCD#_12") (pintype "passive+no_connect"))
    )
    (net (code "72") (name "unconnected-(U1-DSR#-Pad10)") (class "Default")
      (node (ref "U1") (pin "10") (pinfunction "DSR#_10") (pintype "passive+no_connect"))
    )
    (net (code "73") (name "unconnected-(U1-NC-Pad7)") (class "Default")
      (node (ref "U1") (pin "7") (pinfunction "NC_7") (pintype "passive+no_connect"))
    )
    (net (code "74") (name "unconnected-(U1-NC-Pad8)") (class "Default")
      (node (ref "U1") (pin "8") (pinfunction "NC_8") (pintype "passive+no_connect"))
    )
    (net (code "75") (name "unconnected-(U1-R232-Pad15)") (class "Default")
      (node (ref "U1") (pin "15") (pinfunction "R232_15") (pintype "passive+no_connect"))
    )
    (net (code "76") (name "unconnected-(U1-RI#-Pad11)") (class "Default")
      (node (ref "U1") (pin "11") (pinfunction "RI#_11") (pintype "passive+no_connect"))
    )
    (net (code "77") (name "unconnected-(USB1-ID-Pad4)") (class "Default")
      (node (ref "USB1") (pin "4") (pinfunction "ID_4") (pintype "passive+no_connect"))
    )
  )
)
